# SPV1040_v1_0.net
KiCad netlist of a schematic drawn in EAGLE
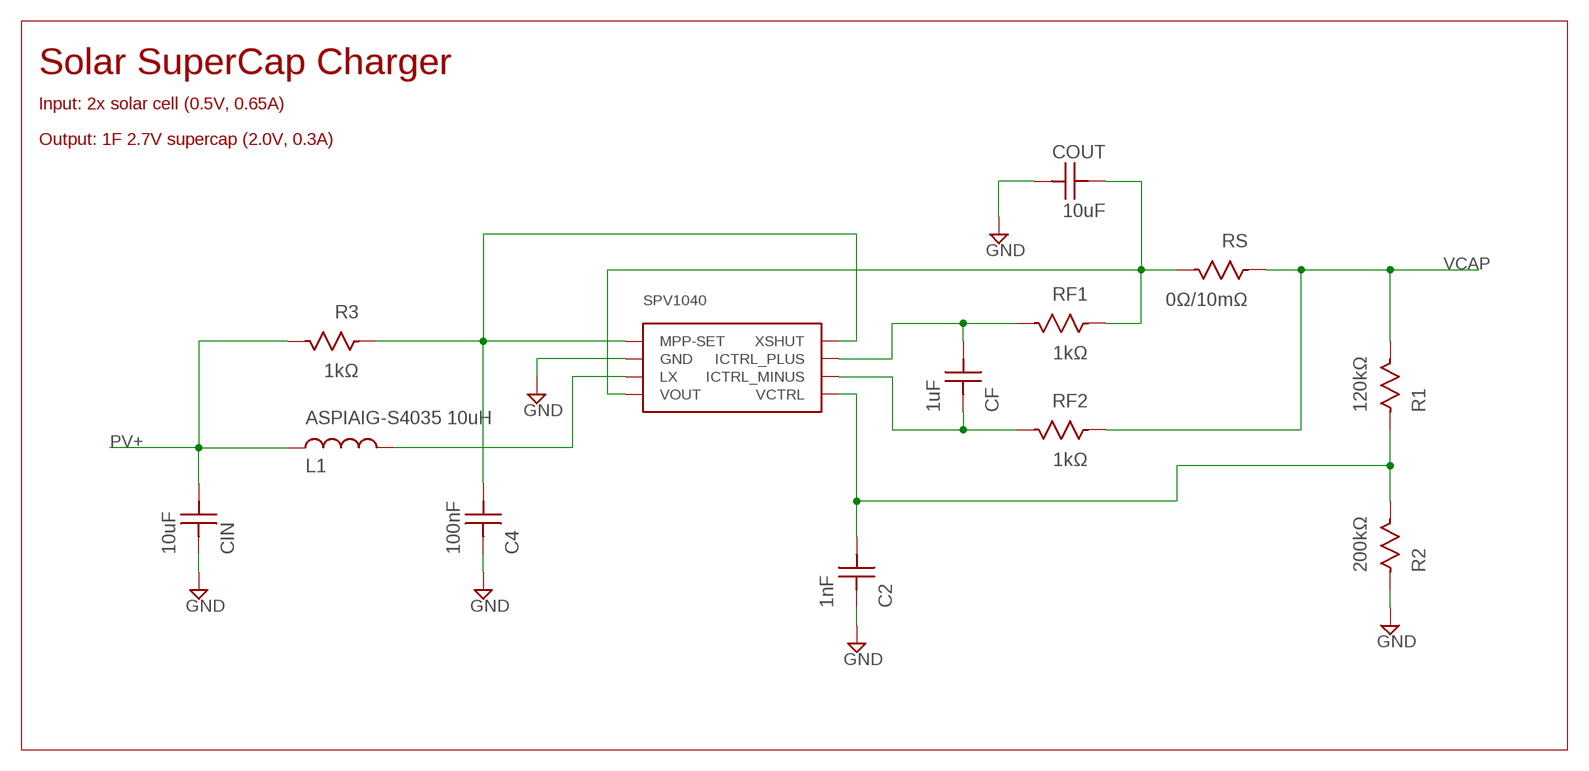
[diagram p0: schematic, sheet 1]

(export (version "E")
  (design (tool "Eeschema 10.0.6"))
  (components
    (comp (ref "C2")
      (value "1nF")
      (footprint "eagle-import:CAP0402")
      (libsource (lib "eagle-import") (part "CAP0402"))
    )
    (comp (ref "C4")
      (value "100nF")
      (footprint "eagle-import:CAP0402")
      (libsource (lib "eagle-import") (part "CAP0402"))
    )
    (comp (ref "CF")
      (value "1uF")
      (footprint "eagle-import:CAP0402")
      (libsource (lib "eagle-import") (part "CAP0402"))
    )
    (comp (ref "CIN")
      (value "10uF")
      (footprint "eagle-import:CAP0402")
      (libsource (lib "eagle-import") (part "CAP0402"))
    )
    (comp (ref "COUT")
      (value "10uF")
      (footprint "eagle-import:CAP0402")
      (libsource (lib "eagle-import") (part "CAP0402"))
    )
    (comp (ref "L1")
      (value "ASPIAIG-S4035 10uH")
      (footprint "eagle-import:ASPIAIG-S4035")
      (libsource (lib "eagle-import") (part "ASPIAIG-S4035"))
    )
    (comp (ref "R1")
      (value "120kΩ")
      (footprint "eagle-import:RES0402")
      (libsource (lib "eagle-import") (part "RES0402"))
    )
    (comp (ref "R2")
      (value "200kΩ")
      (footprint "eagle-import:RES0402")
      (libsource (lib "eagle-import") (part "RES0402"))
    )
    (comp (ref "R3")
      (value "1kΩ")
      (footprint "eagle-import:RES0402")
      (libsource (lib "eagle-import") (part "RES0402"))
    )
    (comp (ref "RF1")
      (value "1kΩ")
      (footprint "eagle-import:RES0402")
      (libsource (lib "eagle-import") (part "RES0402"))
    )
    (comp (ref "RF2")
      (value "1kΩ")
      (footprint "eagle-import:RES0402")
      (libsource (lib "eagle-import") (part "RES0402"))
    )
    (comp (ref "RS")
      (value "0Ω/10mΩ")
      (footprint "eagle-import:RES0402")
      (libsource (lib "eagle-import") (part "RES0402"))
    )
    (comp (ref "U1")
      (value "SPV1040")
      (footprint "eagle-import:SPV1040")
      (libsource (lib "eagle-import") (part "SPV1040"))
    )
  )
  (nets
    (net (code "1") (name "/PV+") (class "Default")
      (node (ref "CIN") (pin "P$2") (pinfunction "P$2_P$2") (pintype "bidirectional"))
      (node (ref "L1") (pin "P$1") (pinfunction "P$1_P$1") (pintype "bidirectional"))
      (node (ref "R3") (pin "P$2") (pinfunction "P$2_P$2") (pintype "bidirectional"))
    )
    (net (code "2") (name "/VCAP") (class "Default")
      (node (ref "R1") (pin "P$2") (pinfunction "P$2_P$2") (pintype "bidirectional"))
      (node (ref "RF2") (pin "P$1") (pinfunction "P$1_P$1") (pintype "bidirectional"))
      (node (ref "RS") (pin "P$1") (pinfunction "P$1_P$1") (pintype "bidirectional"))
    )
    (net (code "3") (name "GND") (class "Default")
      (node (ref "C2") (pin "P$1") (pinfunction "P$1_P$1") (pintype "bidirectional"))
      (node (ref "C4") (pin "P$1") (pinfunction "P$1_P$1") (pintype "bidirectional"))
      (node (ref "CIN") (pin "P$1") (pinfunction "P$1_P$1") (pintype "bidirectional"))
      (node (ref "COUT") (pin "P$2") (pinfunction "P$2_P$2") (pintype "bidirectional"))
      (node (ref "R2") (pin "P$1") (pinfunction "P$1_P$1") (pintype "bidirectional"))
      (node (ref "U1") (pin "GND") (pinfunction "GND_GND") (pintype "bidirectional"))
    )
    (net (code "4") (name "Net-(C2-PadP$2)") (class "Default")
      (node (ref "C2") (pin "P$2") (pinfunction "P$2_P$2") (pintype "bidirectional"))
      (node (ref "R1") (pin "P$1") (pinfunction "P$1_P$1") (pintype "bidirectional"))
      (node (ref "R2") (pin "P$2") (pinfunction "P$2_P$2") (pintype "bidirectional"))
      (node (ref "U1") (pin "VCTRL") (pinfunction "VCTRL_VCTRL") (pintype "bidirectional"))
    )
    (net (code "5") (name "Net-(C4-PadP$2)") (class "Default")
      (node (ref "C4") (pin "P$2") (pinfunction "P$2_P$2") (pintype "bidirectional"))
      (node (ref "R3") (pin "P$1") (pinfunction "P$1_P$1") (pintype "bidirectional"))
      (node (ref "U1") (pin "MPP-SET") (pinfunction "MPP-SET_MPP-SET") (pintype "bidirectional"))
      (node (ref "U1") (pin "XSHUT") (pinfunction "XSHUT_XSHUT") (pintype "bidirectional"))
    )
    (net (code "6") (name "Net-(CF-PadP$1)") (class "Default")
      (node (ref "CF") (pin "P$1") (pinfunction "P$1_P$1") (pintype "bidirectional"))
      (node (ref "RF2") (pin "P$2") (pinfunction "P$2_P$2") (pintype "bidirectional"))
      (node (ref "U1") (pin "ICTRL_MINUS") (pinfunction "ICTRL_MINUS_ICTRL_MINUS") (pintype "bidirectional"))
    )
    (net (code "7") (name "Net-(CF-PadP$2)") (class "Default")
      (node (ref "CF") (pin "P$2") (pinfunction "P$2_P$2") (pintype "bidirectional"))
      (node (ref "RF1") (pin "P$2") (pinfunction "P$2_P$2") (pintype "bidirectional"))
      (node (ref "U1") (pin "ICTRL_PLUS") (pinfunction "ICTRL_PLUS_ICTRL_PLUS") (pintype "bidirectional"))
    )
    (net (code "8") (name "Net-(COUT-PadP$1)") (class "Default")
      (node (ref "COUT") (pin "P$1") (pinfunction "P$1_P$1") (pintype "bidirectional"))
      (node (ref "RF1") (pin "P$1") (pinfunction "P$1_P$1") (pintype "bidirectional"))
      (node (ref "RS") (pin "P$2") (pinfunction "P$2_P$2") (pintype "bidirectional"))
      (node (ref "U1") (pin "VOUT") (pinfunction "VOUT_VOUT") (pintype "bidirectional"))
    )
    (net (code "9") (name "Net-(L1-PadP$2)") (class "Default")
      (node (ref "L1") (pin "P$2") (pinfunction "P$2_P$2") (pintype "bidirectional"))
      (node (ref "U1") (pin "LX") (pinfunction "LX_LX") (pintype "bidirectional"))
    )
  )
)
